# Sheet6.net
KiCad netlist of a schematic drawn in Altium Designer
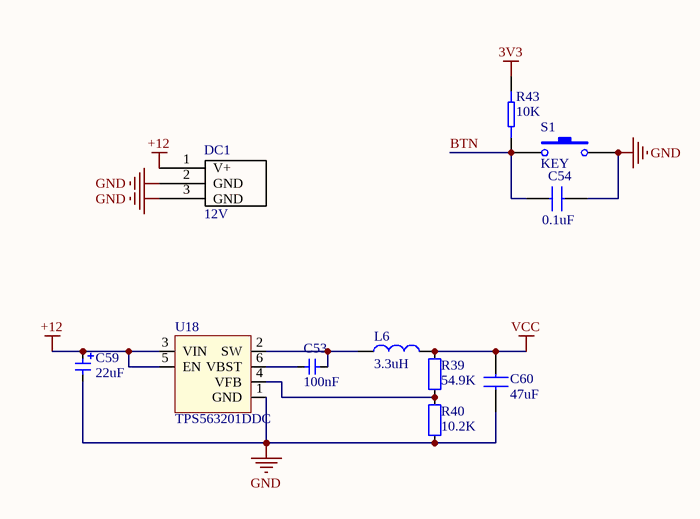
[diagram p0: Sheet6.SchDoc]

(export (version "E")
  (design (tool "Eeschema 10.0.6"))
  (components
    (comp (ref "C53")
      (value "100nF")
      (footprint "CAP_0805")
      (description "Capacitor")
      (libsource (lib "常用原件库") (part "Cap_0805"))
    )
    (comp (ref "C54")
      (value "0.1uF")
      (footprint "0402C")
      (description "SMD-CAP")
      (libsource (lib "Zero") (part "CAP"))
    )
    (comp (ref "C59")
      (value "22uF")
      (footprint "CAP_TAN_B1210")
      (description "Capacitor")
      (libsource (lib "常用原件库") (part "Cap_Tan_1210"))
    )
    (comp (ref "C60")
      (value "47uF")
      (footprint "1206C")
      (description "SMD-CAP")
      (libsource (lib "CTC") (part "CAP"))
    )
    (comp (ref "DC1") (value "12V") (footprint "DC005-2.0MM") (libsource (lib "接插件") (part "DC5V")))
    (comp (ref "L6")
      (value "3.3uH")
      (footprint "SLF10145")
      (description "SLF10145T-3R3N3R7-PF")
      (libsource (lib "CTC") (part "L1"))
    )
    (comp (ref "R39")
      (value "54.9K")
      (footprint "RES_0402")
      (description "Resistor")
      (libsource (lib "常用原件库") (part "Res_0402"))
    )
    (comp (ref "R40")
      (value "10.2K")
      (footprint "RES_0402")
      (description "Resistor")
      (libsource (lib "常用原件库") (part "Res_0402"))
    )
    (comp (ref "R43") (value "10K") (footprint "0402R") (libsource (lib "Zero") (part "R")))
    (comp (ref "S1")
      (value "KEY")
      (footprint "SKHHLVA010")
      (description "SKHHLVA010")
      (fields (field (name "PUBLISHER") "Altium Limited"))
      (libsource (lib "Zero") (part "SW-PB"))
    )
    (comp (ref "U18")
      (value "TPS563201DDC")
      (footprint "SOT23-6")
      (libsource (lib "20180125H1") (part "TPS563201DDC"))
    )
  )
  (nets
    (net (code "1") (name "+12") (class "Default")
      (node (ref "C59") (pin "1") (pinfunction "1_1") (pintype "passive"))
      (node (ref "DC1") (pin "1") (pinfunction "V+_1") (pintype "passive"))
      (node (ref "U18") (pin "3") (pinfunction "VIN_3") (pintype "passive"))
      (node (ref "U18") (pin "5") (pinfunction "EN_5") (pintype "passive"))
    )
    (net (code "2") (name "/BTN") (class "Default")
      (node (ref "C54") (pin "1") (pinfunction "1_1") (pintype "passive"))
      (node (ref "R43") (pin "1") (pinfunction "1_1") (pintype "passive"))
      (node (ref "S1") (pin "1") (pinfunction "1_1") (pintype "passive"))
    )
    (net (code "3") (name "3V3") (class "Default")
      (node (ref "R43") (pin "2") (pinfunction "2_2") (pintype "passive"))
    )
    (net (code "4") (name "GND") (class "Default")
      (node (ref "C54") (pin "2") (pinfunction "2_2") (pintype "passive"))
      (node (ref "C59") (pin "2") (pinfunction "2_2") (pintype "passive"))
      (node (ref "C60") (pin "2") (pinfunction "2_2") (pintype "passive"))
      (node (ref "DC1") (pin "2") (pinfunction "GND_2") (pintype "passive"))
      (node (ref "DC1") (pin "3") (pinfunction "GND_3") (pintype "passive"))
      (node (ref "R40") (pin "1") (pinfunction "1_1") (pintype "passive"))
      (node (ref "S1") (pin "2") (pinfunction "2_2") (pintype "passive"))
      (node (ref "U18") (pin "1") (pinfunction "GND_1") (pintype "passive"))
    )
    (net (code "5") (name "Net-(U18-SW)") (class "Default")
      (node (ref "C53") (pin "2") (pinfunction "2_2") (pintype "passive"))
      (node (ref "L6") (pin "2") (pinfunction "2_2") (pintype "passive"))
      (node (ref "U18") (pin "2") (pinfunction "SW_2") (pintype "passive"))
    )
    (net (code "6") (name "Net-(U18-VBST)") (class "Default")
      (node (ref "C53") (pin "1") (pinfunction "1_1") (pintype "passive"))
      (node (ref "U18") (pin "6") (pinfunction "VBST_6") (pintype "passive"))
    )
    (net (code "7") (name "Net-(U18-VFB)") (class "Default")
      (node (ref "R39") (pin "1") (pinfunction "1_1") (pintype "passive"))
      (node (ref "R40") (pin "2") (pinfunction "2_2") (pintype "passive"))
      (node (ref "U18") (pin "4") (pinfunction "VFB_4") (pintype "passive"))
    )
    (net (code "8") (name "VCC") (class "Default")
      (node (ref "C60") (pin "1") (pinfunction "1_1") (pintype "passive"))
      (node (ref "L6") (pin "1") (pinfunction "1_1") (pintype "passive"))
      (node (ref "R39") (pin "2") (pinfunction "2_2") (pintype "passive"))
    )
  )
)
